# gpz.net
KiCad netlist of a schematic drawn in Altium Designer
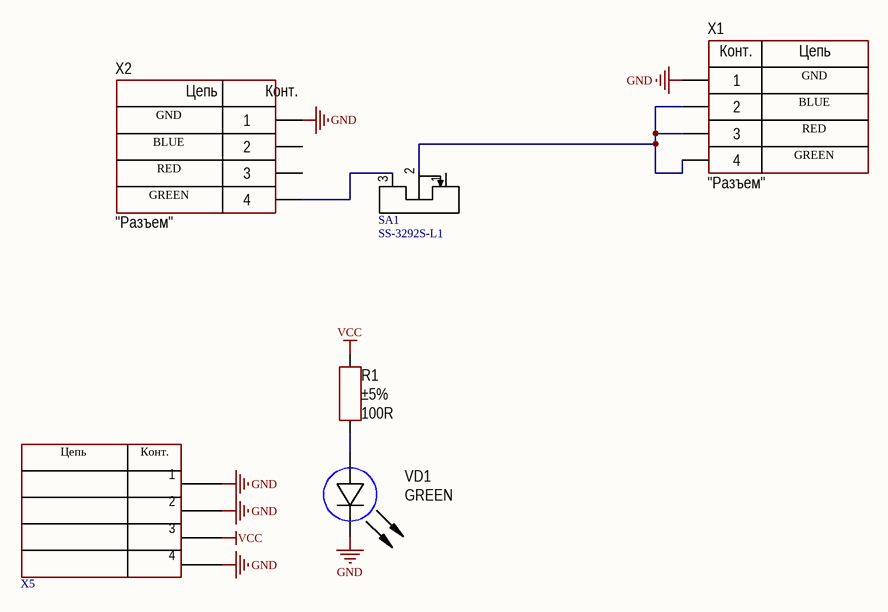
[diagram p0: gpz.SchDoc]

(export (version "E")
  (design (tool "Eeschema 10.0.6"))
  (components
    (comp (ref "R1")
      (value "100R")
      (footprint "RES: 0603")
      (fields
        (field (name "MANUFACTURER") "Yageo")
        (field (name "PARTNUMBER") "RC0603JR-07100RL")
        (field (name "VALUEMANUFACTURERPARTNUMBER") "Resistor film, 100R, ±5%, 0603, 0.1W, -55...+125°C")
        (field (name "TOLERANCE") "±5%")
      )
      (libsource (lib "Resistor") (part "Resistor_0603"))
    )
    (comp (ref "SA1")
      (value "SS-3292S-L1")
      (footprint "SS-3292S-L1")
      (libsource (lib "switch") (part "SS-3292S-L1"))
    )
    (comp (ref "VD1")
      (value "~")
      (footprint "LED: 0805G")
      (fields
        (field (name "VALUEMANUFACTURERPARTNUMBER") "LED, *, *, *, -55...+150°C")
        (field (name "COLOR") "GREEN")
      )
      (libsource (lib "Diode") (part "LED_single"))
    )
    (comp (ref "X1")
      (value "~")
      (footprint "4PLS RIGHT ANGLE 2")
      (fields
        (field (name "MANUFACTURER") "Connfly")
        (field (name "VALUEMANUFACTURERPARTNUMBER") "Connector, 4pin, 2.54mm, 500VAC, 3A")
        (field (name "PARTNUMBER") "PLS-4")
        (field (name "COMMENTTEXT") "\"Разъем\"")
      )
      (libsource (lib "Connector") (part "PLS-4"))
    )
    (comp (ref "X2")
      (value "~")
      (footprint "CON: PBS-4 R")
      (fields
        (field (name "MANUFACTURER") "Connfly")
        (field (name "VALUEMANUFACTURERPARTNUMBER") "Connector, 4pin, 2.54mm, 500VAC, 3A")
        (field (name "PARTNUMBER") "PBS-4")
        (field (name "COMMENTTEXT") "\"Разъем\"")
      )
      (libsource (lib "Connector") (part "PBS-4"))
    )
    (comp (ref "X5")
      (value "PBS-4 cut")
      (footprint "PBS-4 CUT")
      (libsource (lib "conect") (part "PBS-4 cut"))
    )
  )
  (nets
    (net (code "1") (name "GND") (class "Default")
      (node (ref "VD1") (pin "2") (pinfunction "C_2") (pintype "passive"))
      (node (ref "X1") (pin "1") (pinfunction "1_1") (pintype "passive"))
      (node (ref "X2") (pin "1") (pinfunction "1_1") (pintype "passive"))
      (node (ref "X5") (pin "1") (pinfunction "1_1") (pintype "passive"))
      (node (ref "X5") (pin "2") (pinfunction "2_2") (pintype "passive"))
      (node (ref "X5") (pin "4") (pinfunction "4_4") (pintype "passive"))
    )
    (net (code "2") (name "Net-(SA1-Pad2)") (class "Default")
      (node (ref "SA1") (pin "2") (pinfunction "2_2") (pintype "passive"))
      (node (ref "X1") (pin "2") (pinfunction "2_2") (pintype "passive"))
      (node (ref "X1") (pin "3") (pinfunction "3_3") (pintype "power_in"))
      (node (ref "X1") (pin "4") (pinfunction "4_4") (pintype "power_in"))
    )
    (net (code "3") (name "Net-(SA1-Pad3)") (class "Default")
      (node (ref "SA1") (pin "3") (pinfunction "3_3") (pintype "passive"))
      (node (ref "X2") (pin "4") (pinfunction "4_4") (pintype "power_in"))
    )
    (net (code "4") (name "Net-(VD1-A)") (class "Default")
      (node (ref "R1") (pin "1") (pinfunction "1_1") (pintype "passive"))
      (node (ref "VD1") (pin "1") (pinfunction "A_1") (pintype "passive"))
    )
    (net (code "5") (name "VCC") (class "Default")
      (node (ref "R1") (pin "2") (pinfunction "2_2") (pintype "passive"))
      (node (ref "X5") (pin "3") (pinfunction "3_3") (pintype "passive"))
    )
    (net (code "6") (name "unconnected-(SA1-Pad1)") (class "Default")
      (node (ref "SA1") (pin "1") (pinfunction "1_1") (pintype "passive"))
    )
    (net (code "7") (name "unconnected-(X2-Pad2)") (class "Default")
      (node (ref "X2") (pin "2") (pinfunction "2_2") (pintype "passive"))
    )
    (net (code "8") (name "unconnected-(X2-Pad3)") (class "Default")
      (node (ref "X2") (pin "3") (pinfunction "3_3") (pintype "power_in"))
    )
  )
)
